# Power_POE.net
KiCad netlist of a schematic drawn in EAGLE
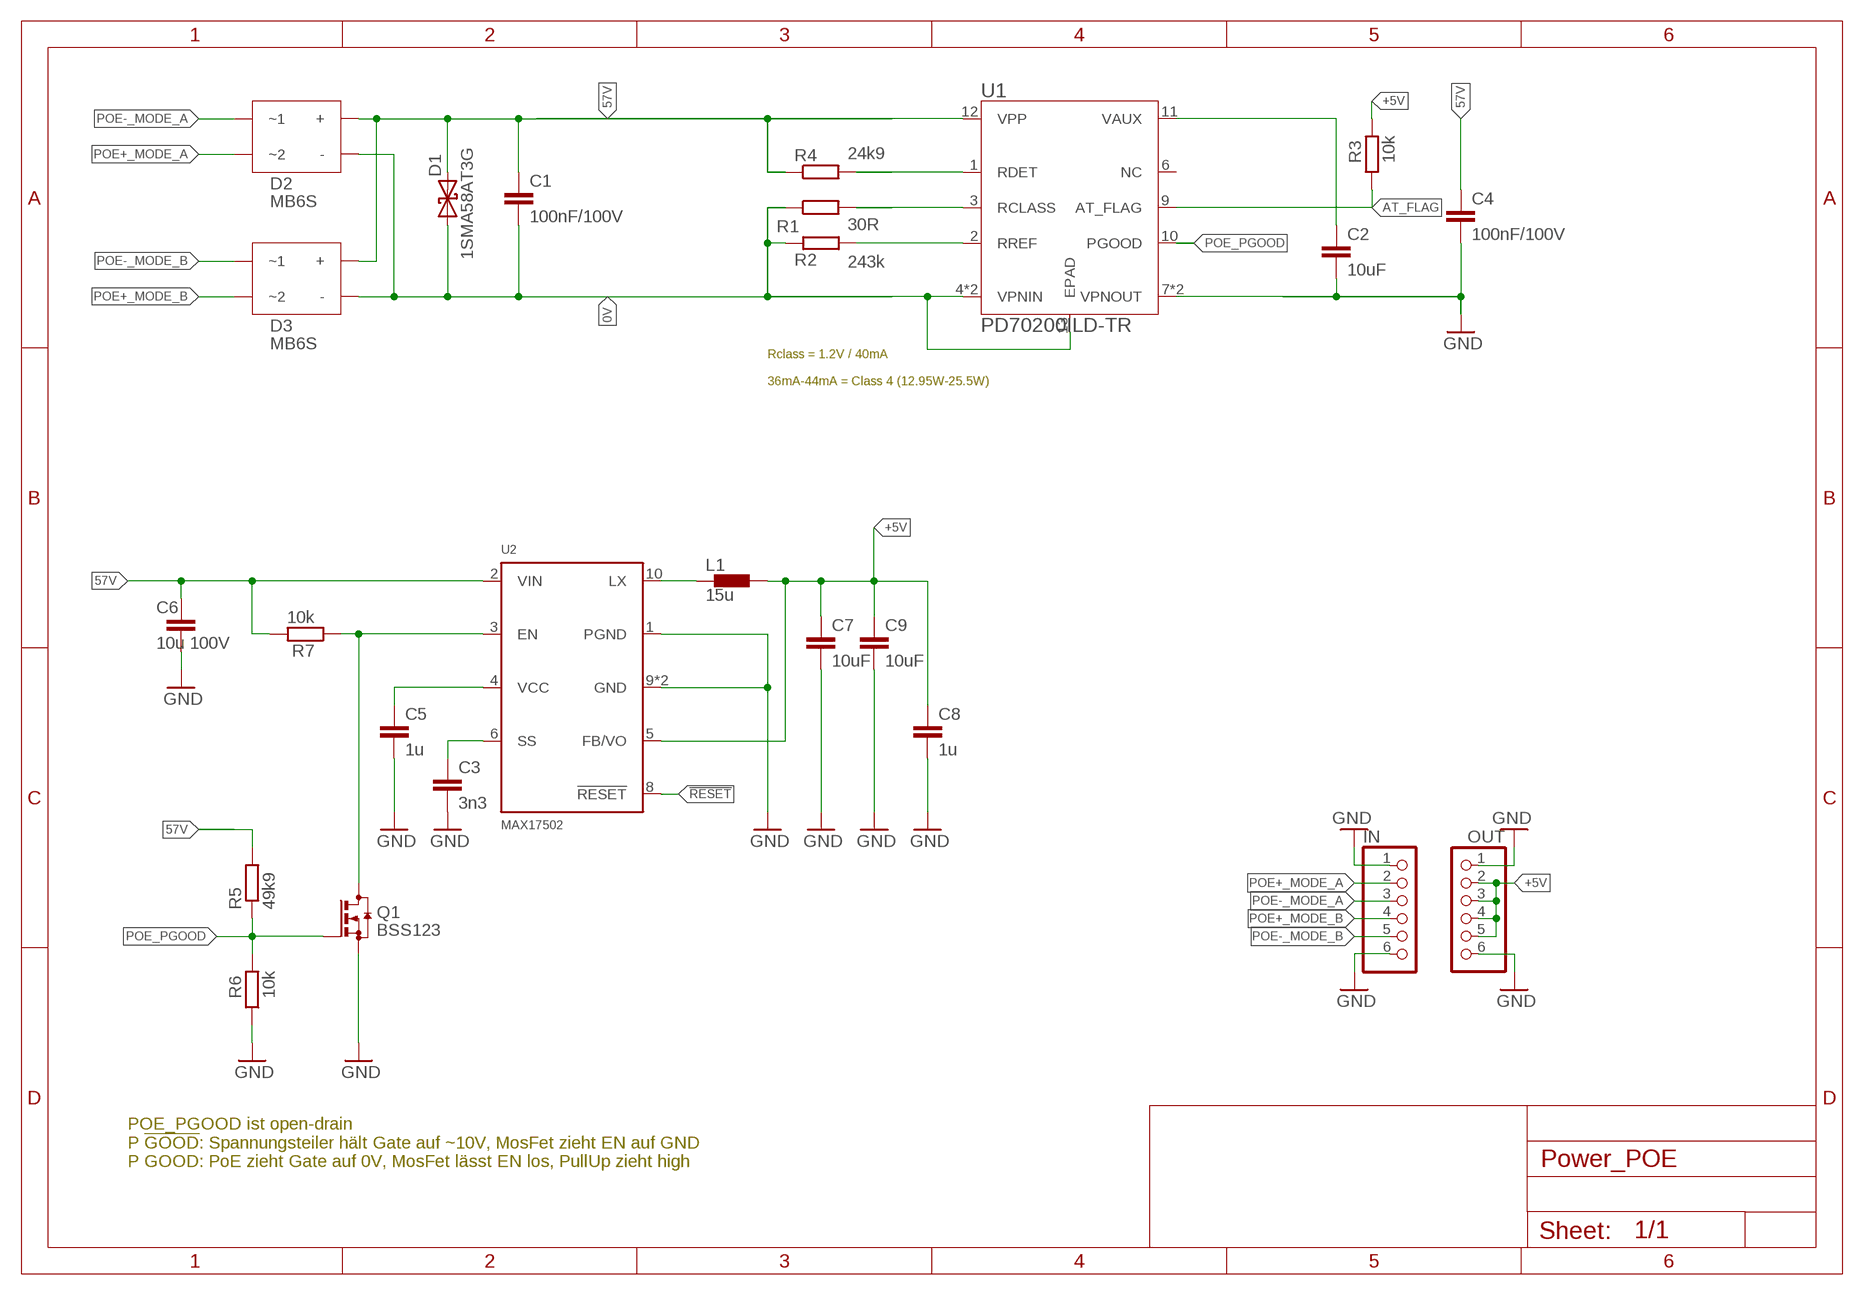
[diagram p0: schematic, sheet 1]

(export (version "E")
  (design (tool "Eeschema 10.0.6"))
  (components
    (comp (ref "C1")
      (value "100nF/100V")
      (footprint "eagle-import:C0603")
      (libsource (lib "eagle-import") (part "C-EUC0603"))
    )
    (comp (ref "C2")
      (value "10uF")
      (footprint "eagle-import:C0805")
      (libsource (lib "eagle-import") (part "rcl_334_C-EUC0805"))
    )
    (comp (ref "C3")
      (value "3n3")
      (footprint "eagle-import:C0603")
      (libsource (lib "eagle-import") (part "C-EUC0603"))
    )
    (comp (ref "C4")
      (value "100nF/100V")
      (footprint "eagle-import:C0603")
      (libsource (lib "eagle-import") (part "C-EUC0603"))
    )
    (comp (ref "C5")
      (value "1u")
      (footprint "eagle-import:C0805")
      (libsource (lib "eagle-import") (part "C-EUC0805"))
    )
    (comp (ref "C6")
      (value "10u 100V")
      (footprint "eagle-import:C1210K")
      (libsource (lib "eagle-import") (part "rcl_334_C-EUC1210K"))
    )
    (comp (ref "C7")
      (value "10uF")
      (footprint "eagle-import:C0805")
      (libsource (lib "eagle-import") (part "rcl_334_C-EUC0805"))
    )
    (comp (ref "C8")
      (value "1u")
      (footprint "eagle-import:C0805")
      (libsource (lib "eagle-import") (part "C-EUC0805"))
    )
    (comp (ref "C9")
      (value "10uF")
      (footprint "eagle-import:C0805")
      (libsource (lib "eagle-import") (part "rcl_334_C-EUC0805"))
    )
    (comp (ref "D1")
      (value "1SMA58AT3G")
      (footprint "eagle-import:DO214AC")
      (fields (field (name "MF") "Littlefuse") (field (name "MPN") "SMAJ58A"))
      (libsource (lib "eagle-import") (part "SMAJ_DIODE"))
    )
    (comp (ref "D2")
      (value "MB6S")
      (footprint "eagle-import:SOIC4W")
      (libsource (lib "eagle-import") (part "MB6S"))
    )
    (comp (ref "D3")
      (value "MB6S")
      (footprint "eagle-import:SOIC4W")
      (libsource (lib "eagle-import") (part "MB6S"))
    )
    (comp (ref "IN")
      (value "PINHD-1X06_2.00")
      (footprint "eagle-import:1X06M")
      (libsource (lib "eagle-import") (part "PINHD-1X06_2.00"))
    )
    (comp (ref "L1")
      (value "15u")
      (footprint "eagle-import:LPS6235")
      (fields (field (name "MPN") "LPS6235-153MRC"))
      (libsource (lib "eagle-import") (part "INDUCTOR_LPS6235"))
    )
    (comp (ref "OUT")
      (value "PINHD-1X06_2.00")
      (footprint "eagle-import:1X06M")
      (libsource (lib "eagle-import") (part "PINHD-1X06_2.00"))
    )
    (comp (ref "Q1")
      (value "BSS123")
      (footprint "eagle-import:SOT23")
      (libsource (lib "eagle-import") (part "BSS123"))
    )
    (comp (ref "R1")
      (value "30R")
      (footprint "eagle-import:R0603")
      (libsource (lib "eagle-import") (part "rcl_334_R-EU_R0603"))
    )
    (comp (ref "R2")
      (value "243k")
      (footprint "eagle-import:R0603")
      (libsource (lib "eagle-import") (part "rcl_334_R-EU_R0603"))
    )
    (comp (ref "R3")
      (value "10k")
      (footprint "eagle-import:R0603")
      (libsource (lib "eagle-import") (part "R-EU_R0603"))
    )
    (comp (ref "R4")
      (value "24k9")
      (footprint "eagle-import:R0603")
      (libsource (lib "eagle-import") (part "rcl_334_R-EU_R0603"))
    )
    (comp (ref "R5")
      (value "49k9")
      (footprint "eagle-import:R0603")
      (libsource (lib "eagle-import") (part "rcl_334_R-EU_R0603"))
    )
    (comp (ref "R6")
      (value "10k")
      (footprint "eagle-import:R0603")
      (libsource (lib "eagle-import") (part "R-EU_R0603"))
    )
    (comp (ref "R7")
      (value "10k")
      (footprint "eagle-import:R0603")
      (libsource (lib "eagle-import") (part "R-EU_R0603"))
    )
    (comp (ref "U1")
      (value "PD70200ILD-TR")
      (footprint "eagle-import:DFN12_4X3_MIS")
      (libsource (lib "eagle-import") (part "PD70200ILD-TR"))
    )
    (comp (ref "U2")
      (value "MAX17502")
      (footprint "eagle-import:TDFN10-3X2MM")
      (fields (field (name "MPN") "MAX17502EATB+T"))
      (libsource (lib "eagle-import") (part "MAX17502"))
    )
  )
  (nets
    (net (code "1") (name "+5V") (class "Default")
      (node (ref "C7") (pin "1") (pinfunction "1_1") (pintype "passive"))
      (node (ref "C8") (pin "1") (pinfunction "1_1") (pintype "passive"))
      (node (ref "C9") (pin "1") (pinfunction "1_1") (pintype "passive"))
      (node (ref "L1") (pin "2") (pinfunction "2_2") (pintype "passive"))
      (node (ref "OUT") (pin "2") (pinfunction "2_2") (pintype "passive"))
      (node (ref "OUT") (pin "3") (pinfunction "3_3") (pintype "passive"))
      (node (ref "OUT") (pin "4") (pinfunction "4_4") (pintype "passive"))
      (node (ref "OUT") (pin "5") (pinfunction "5_5") (pintype "passive"))
      (node (ref "R3") (pin "2") (pinfunction "2_2") (pintype "passive"))
      (node (ref "U2") (pin "5") (pinfunction "FB/VO_5") (pintype "passive"))
    )
    (net (code "2") (name "/~{RESET}") (class "Default")
      (node (ref "U2") (pin "8") (pinfunction "~{RESET}_8") (pintype "input"))
    )
    (net (code "3") (name "0V") (class "Default")
      (node (ref "C1") (pin "2") (pinfunction "2_2") (pintype "passive"))
      (node (ref "D1") (pin "A") (pinfunction "1_A") (pintype "passive"))
      (node (ref "D2") (pin "P$2") (pinfunction "-_P$2") (pintype "bidirectional"))
      (node (ref "D3") (pin "P$2") (pinfunction "-_P$2") (pintype "bidirectional"))
      (node (ref "R1") (pin "1") (pinfunction "1_1") (pintype "passive"))
      (node (ref "R2") (pin "1") (pinfunction "1_1") (pintype "passive"))
      (node (ref "U1") (pin "13") (pinfunction "EPAD_13") (pintype "passive"))
      (node (ref "U1") (pin "4") (pinfunction "VPNIN_4") (pintype "input"))
      (node (ref "U1") (pin "5") (pinfunction "VPNIN_5") (pintype "input"))
    )
    (net (code "4") (name "57V") (class "Default")
      (node (ref "C1") (pin "1") (pinfunction "1_1") (pintype "passive"))
      (node (ref "C4") (pin "1") (pinfunction "1_1") (pintype "passive"))
      (node (ref "C6") (pin "1") (pinfunction "1_1") (pintype "passive"))
      (node (ref "D1") (pin "C") (pinfunction "2_C") (pintype "passive"))
      (node (ref "D2") (pin "P$1") (pinfunction "+_P$1") (pintype "bidirectional"))
      (node (ref "D3") (pin "P$1") (pinfunction "+_P$1") (pintype "bidirectional"))
      (node (ref "R4") (pin "1") (pinfunction "1_1") (pintype "passive"))
      (node (ref "R5") (pin "2") (pinfunction "2_2") (pintype "passive"))
      (node (ref "R7") (pin "2") (pinfunction "2_2") (pintype "passive"))
      (node (ref "U1") (pin "12") (pinfunction "VPP_12") (pintype "power_in"))
      (node (ref "U2") (pin "2") (pinfunction "VIN_2") (pintype "power_in"))
    )
    (net (code "5") (name "AT_FLAG") (class "Default")
      (node (ref "R3") (pin "1") (pinfunction "1_1") (pintype "passive"))
      (node (ref "U1") (pin "9") (pinfunction "AT_FLAG_9") (pintype "passive"))
    )
    (net (code "6") (name "GND") (class "Default")
      (node (ref "C2") (pin "2") (pinfunction "2_2") (pintype "passive"))
      (node (ref "C3") (pin "2") (pinfunction "2_2") (pintype "passive"))
      (node (ref "C4") (pin "2") (pinfunction "2_2") (pintype "passive"))
      (node (ref "C5") (pin "2") (pinfunction "2_2") (pintype "passive"))
      (node (ref "C6") (pin "2") (pinfunction "2_2") (pintype "passive"))
      (node (ref "C7") (pin "2") (pinfunction "2_2") (pintype "passive"))
      (node (ref "C8") (pin "2") (pinfunction "2_2") (pintype "passive"))
      (node (ref "C9") (pin "2") (pinfunction "2_2") (pintype "passive"))
      (node (ref "IN") (pin "1") (pinfunction "1_1") (pintype "passive"))
      (node (ref "IN") (pin "6") (pinfunction "6_6") (pintype "passive"))
      (node (ref "OUT") (pin "1") (pinfunction "1_1") (pintype "passive"))
      (node (ref "OUT") (pin "6") (pinfunction "6_6") (pintype "passive"))
      (node (ref "Q1") (pin "2") (pinfunction "S_2") (pintype "passive"))
      (node (ref "R6") (pin "1") (pinfunction "1_1") (pintype "passive"))
      (node (ref "U1") (pin "7") (pinfunction "VPNOUT_7") (pintype "output"))
      (node (ref "U1") (pin "8") (pinfunction "VPNOUT_8") (pintype "output"))
      (node (ref "U2") (pin "1") (pinfunction "PGND_1") (pintype "power_in"))
      (node (ref "U2") (pin "9") (pinfunction "GND_9") (pintype "power_in"))
      (node (ref "U2") (pin "TH") (pinfunction "GND_TH") (pintype "power_in"))
    )
    (net (code "7") (name "Net-(Q1-D)") (class "Default")
      (node (ref "Q1") (pin "3") (pinfunction "D_3") (pintype "passive"))
      (node (ref "R7") (pin "1") (pinfunction "1_1") (pintype "passive"))
      (node (ref "U2") (pin "3") (pinfunction "EN_3") (pintype "input"))
    )
    (net (code "8") (name "Net-(U1-RCLASS)") (class "Default")
      (node (ref "R1") (pin "2") (pinfunction "2_2") (pintype "passive"))
      (node (ref "U1") (pin "3") (pinfunction "RCLASS_3") (pintype "passive"))
    )
    (net (code "9") (name "Net-(U1-RDET)") (class "Default")
      (node (ref "R4") (pin "2") (pinfunction "2_2") (pintype "passive"))
      (node (ref "U1") (pin "1") (pinfunction "RDET_1") (pintype "passive"))
    )
    (net (code "10") (name "Net-(U1-RREF)") (class "Default")
      (node (ref "R2") (pin "2") (pinfunction "2_2") (pintype "passive"))
      (node (ref "U1") (pin "2") (pinfunction "RREF_2") (pintype "passive"))
    )
    (net (code "11") (name "Net-(U1-VAUX)") (class "Default")
      (node (ref "C2") (pin "1") (pinfunction "1_1") (pintype "passive"))
      (node (ref "U1") (pin "11") (pinfunction "VAUX_11") (pintype "power_in"))
    )
    (net (code "12") (name "Net-(U2-LX)") (class "Default")
      (node (ref "L1") (pin "1") (pinfunction "1_1") (pintype "passive"))
      (node (ref "U2") (pin "10") (pinfunction "LX_10") (pintype "output"))
    )
    (net (code "13") (name "Net-(U2-SS)") (class "Default")
      (node (ref "C3") (pin "1") (pinfunction "1_1") (pintype "passive"))
      (node (ref "U2") (pin "6") (pinfunction "SS_6") (pintype "passive"))
    )
    (net (code "14") (name "Net-(U2-VCC)") (class "Default")
      (node (ref "C5") (pin "1") (pinfunction "1_1") (pintype "passive"))
      (node (ref "U2") (pin "4") (pinfunction "VCC_4") (pintype "power_in"))
    )
    (net (code "15") (name "POE+_MODE_A") (class "Default")
      (node (ref "D2") (pin "P$4") (pinfunction "~{2}_P$4") (pintype "bidirectional"))
      (node (ref "IN") (pin "2") (pinfunction "2_2") (pintype "passive"))
    )
    (net (code "16") (name "POE+_MODE_B") (class "Default")
      (node (ref "D3") (pin "P$4") (pinfunction "~{2}_P$4") (pintype "bidirectional"))
      (node (ref "IN") (pin "4") (pinfunction "4_4") (pintype "passive"))
    )
    (net (code "17") (name "POE-_MODE_A") (class "Default")
      (node (ref "D2") (pin "P$3") (pinfunction "~{1}_P$3") (pintype "bidirectional"))
      (node (ref "IN") (pin "3") (pinfunction "3_3") (pintype "passive"))
    )
    (net (code "18") (name "POE-_MODE_B") (class "Default")
      (node (ref "D3") (pin "P$3") (pinfunction "~{1}_P$3") (pintype "bidirectional"))
      (node (ref "IN") (pin "5") (pinfunction "5_5") (pintype "passive"))
    )
    (net (code "19") (name "POE_PGOOD") (class "Default")
      (node (ref "Q1") (pin "1") (pinfunction "G_1") (pintype "passive"))
      (node (ref "R5") (pin "1") (pinfunction "1_1") (pintype "passive"))
      (node (ref "R6") (pin "2") (pinfunction "2_2") (pintype "passive"))
      (node (ref "U1") (pin "10") (pinfunction "PGOOD_10") (pintype "passive"))
    )
    (net (code "20") (name "unconnected-(U1-NC-Pad6)") (class "Default")
      (node (ref "U1") (pin "6") (pinfunction "NC_6") (pintype "no_connect"))
    )
  )
)
